# 04-mcu2.net
KiCad netlist of a schematic drawn in Altium Designer
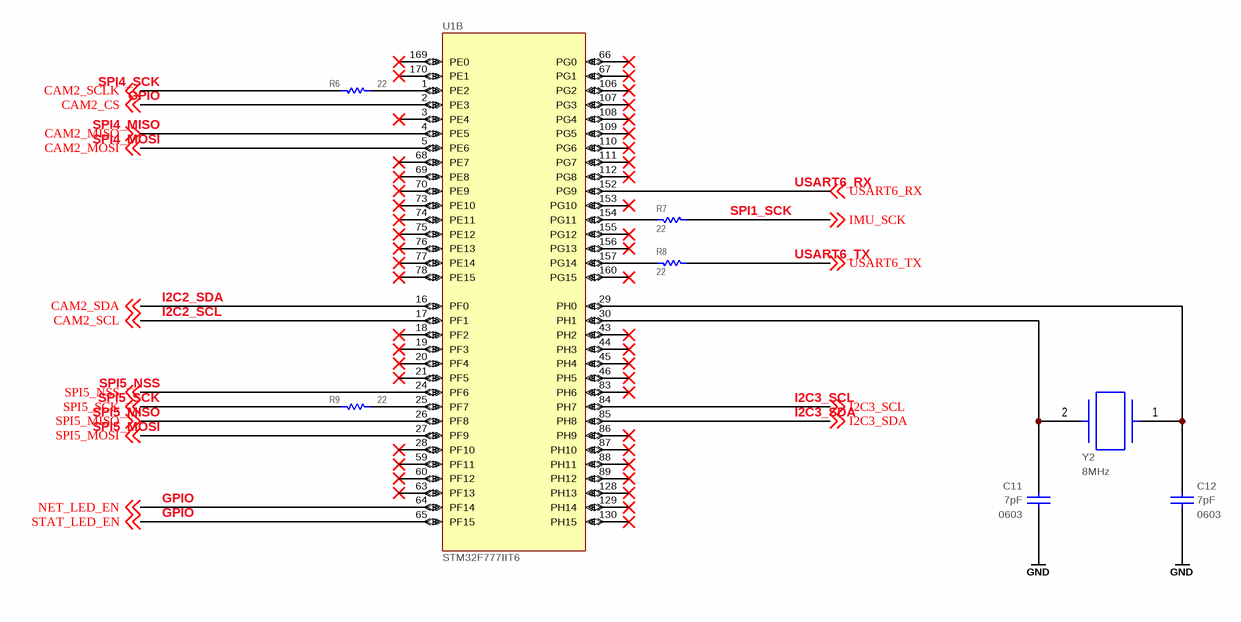
[diagram p0: 04-mcu2.SchDoc]

(export (version "E")
  (design (tool "Eeschema 10.0.6"))
  (components
    (comp (ref "C11")
      (value "7pF")
      (footprint "generic:CAPC160X80X90L20N")
      (description "Ceramic Capacitor 7pF +/-0.25pF 0603")
      (fields
        (field (name "MANUFACTURER") "Samsung")
        (field (name "TOLERANCE") "+/-0.25pF")
        (field (name "PACKAGE") "0603")
      )
      (libsource (lib "vishay") (part "CAP"))
    )
    (comp (ref "C12")
      (value "7pF")
      (footprint "generic:CAPC160X80X90L20N")
      (description "Ceramic Capacitor 7pF +/-0.25pF 0603")
      (fields
        (field (name "MANUFACTURER") "Samsung")
        (field (name "TOLERANCE") "+/-0.25pF")
        (field (name "PACKAGE") "0603")
      )
      (libsource (lib "vishay") (part "CAP"))
    )
    (comp (ref "R6")
      (value "22")
      (footprint "RESC2012X70N")
      (description "Thick Film Resistor 22 ±1% 0805")
      (fields (field (name "MANUFACTURER") "Panasonic") (field (name "TOLERANCE") "±1%"))
      (libsource (lib "Graviton") (part "RES 0402"))
    )
    (comp (ref "R7")
      (value "22")
      (footprint "RESC2012X70N")
      (description "Thick Film Resistor 22 ±1% 0805")
      (fields (field (name "MANUFACTURER") "Panasonic") (field (name "TOLERANCE") "±1%"))
      (libsource (lib "Graviton") (part "RES 0402"))
    )
    (comp (ref "R8")
      (value "22")
      (footprint "RESC2012X70N")
      (description "Thick Film Resistor 22 ±1% 0805")
      (fields (field (name "MANUFACTURER") "Panasonic") (field (name "TOLERANCE") "±1%"))
      (libsource (lib "Graviton") (part "RES 0402"))
    )
    (comp (ref "R9")
      (value "22")
      (footprint "RESC2012X70N")
      (description "Thick Film Resistor 22 ±1% 0805")
      (fields (field (name "MANUFACTURER") "Panasonic") (field (name "TOLERANCE") "±1%"))
      (libsource (lib "Graviton") (part "RES 0402"))
    )
    (comp (ref "U1")
      (value "STM32F777IIT6")
      (footprint "st:TSQFP50P2600X2600X160-176N")
      (description "Microcontroller")
      (fields (field (name "MANUFACTURER") "STMicroelectronics"))
      (libsource (lib "st") (part "STM32F777IIT"))
    )
    (comp (ref "Y2")
      (value "ABLS-8.000MHZ-B2-T")
      (footprint "ABLS")
      (description "CRYSTAL 8MHZ 18PF SMD")
      (fields (field (name "MANUFACTURER") "Abracon LLC") (field (name "FREQUENCY") "8MHz"))
      (libsource (lib "abracon") (part "ABLS-8.000MHZ-B2-T"))
    )
  )
  (nets
    (net (code "1") (name "CAM2_CS") (class "Default")
      (node (ref "U1") (pin "2") (pinfunction "PE3_2") (pintype "bidirectional"))
    )
    (net (code "2") (name "CAM2_MISO") (class "Default")
      (node (ref "U1") (pin "4") (pinfunction "PE5_4") (pintype "bidirectional"))
    )
    (net (code "3") (name "CAM2_MOSI") (class "Default")
      (node (ref "U1") (pin "5") (pinfunction "PE6_5") (pintype "bidirectional"))
    )
    (net (code "4") (name "CAM2_SCL") (class "Default")
      (node (ref "U1") (pin "17") (pinfunction "PF1_17") (pintype "bidirectional"))
    )
    (net (code "5") (name "CAM2_SCLK") (class "Default")
      (node (ref "R6") (pin "1") (pinfunction "1_1") (pintype "passive"))
    )
    (net (code "6") (name "CAM2_SDA") (class "Default")
      (node (ref "U1") (pin "16") (pinfunction "PF0_16") (pintype "bidirectional"))
    )
    (net (code "7") (name "GND") (class "Default")
      (node (ref "C11") (pin "1") (pinfunction "1_1") (pintype "passive"))
      (node (ref "C12") (pin "1") (pinfunction "1_1") (pintype "passive"))
    )
    (net (code "8") (name "I2C3_SCL") (class "Default")
      (node (ref "U1") (pin "84") (pinfunction "PH7_84") (pintype "bidirectional"))
    )
    (net (code "9") (name "I2C3_SDA") (class "Default")
      (node (ref "U1") (pin "85") (pinfunction "PH8_85") (pintype "bidirectional"))
    )
    (net (code "10") (name "IMU_SCK") (class "Default")
      (node (ref "R7") (pin "2") (pinfunction "2_2") (pintype "passive"))
    )
    (net (code "11") (name "NET_LED_EN") (class "Default")
      (node (ref "U1") (pin "64") (pinfunction "PF14_64") (pintype "bidirectional"))
    )
    (net (code "12") (name "Net-(U1B-PE2)") (class "Default")
      (node (ref "R6") (pin "2") (pinfunction "2_2") (pintype "passive"))
      (node (ref "U1") (pin "1") (pinfunction "PE2_1") (pintype "bidirectional"))
    )
    (net (code "13") (name "Net-(U1B-PF7)") (class "Default")
      (node (ref "R9") (pin "2") (pinfunction "2_2") (pintype "passive"))
      (node (ref "U1") (pin "25") (pinfunction "PF7_25") (pintype "bidirectional"))
    )
    (net (code "14") (name "Net-(U1B-PG11)") (class "Default")
      (node (ref "R7") (pin "1") (pinfunction "1_1") (pintype "passive"))
      (node (ref "U1") (pin "154") (pinfunction "PG11_154") (pintype "bidirectional"))
    )
    (net (code "15") (name "Net-(U1B-PG14)") (class "Default")
      (node (ref "R8") (pin "1") (pinfunction "1_1") (pintype "passive"))
      (node (ref "U1") (pin "157") (pinfunction "PG14_157") (pintype "bidirectional"))
    )
    (net (code "16") (name "Net-(U1B-PH0)") (class "Default")
      (node (ref "C12") (pin "2") (pinfunction "2_2") (pintype "passive"))
      (node (ref "U1") (pin "29") (pinfunction "PH0_29") (pintype "bidirectional"))
      (node (ref "Y2") (pin "1") (pinfunction "XTAL1_1") (pintype "passive"))
    )
    (net (code "17") (name "Net-(U1B-PH1)") (class "Default")
      (node (ref "C11") (pin "2") (pinfunction "2_2") (pintype "passive"))
      (node (ref "U1") (pin "30") (pinfunction "PH1_30") (pintype "bidirectional"))
      (node (ref "Y2") (pin "2") (pinfunction "XTAL2_2") (pintype "passive"))
    )
    (net (code "18") (name "SPI5_MISO") (class "Default")
      (node (ref "U1") (pin "26") (pinfunction "PF8_26") (pintype "bidirectional"))
    )
    (net (code "19") (name "SPI5_MOSI") (class "Default")
      (node (ref "U1") (pin "27") (pinfunction "PF9_27") (pintype "bidirectional"))
    )
    (net (code "20") (name "SPI5_NSS") (class "Default")
      (node (ref "U1") (pin "24") (pinfunction "PF6_24") (pintype "bidirectional"))
    )
    (net (code "21") (name "SPI5_SCK") (class "Default")
      (node (ref "R9") (pin "1") (pinfunction "1_1") (pintype "passive"))
    )
    (net (code "22") (name "STAT_LED_EN") (class "Default")
      (node (ref "U1") (pin "65") (pinfunction "PF15_65") (pintype "bidirectional"))
    )
    (net (code "23") (name "USART6_RX") (class "Default")
      (node (ref "U1") (pin "152") (pinfunction "PG9_152") (pintype "bidirectional"))
    )
    (net (code "24") (name "USART6_TX") (class "Default")
      (node (ref "R8") (pin "2") (pinfunction "2_2") (pintype "passive"))
    )
    (net (code "25") (name "unconnected-(U1B-PE0-Pad169)") (class "Default")
      (node (ref "U1") (pin "169") (pinfunction "PE0_169") (pintype "bidirectional+no_connect"))
    )
    (net (code "26") (name "unconnected-(U1B-PE1-Pad170)") (class "Default")
      (node (ref "U1") (pin "170") (pinfunction "PE1_170") (pintype "bidirectional+no_connect"))
    )
    (net (code "27") (name "unconnected-(U1B-PE4-Pad3)") (class "Default")
      (node (ref "U1") (pin "3") (pinfunction "PE4_3") (pintype "bidirectional+no_connect"))
    )
    (net (code "28") (name "unconnected-(U1B-PE7-Pad68)") (class "Default")
      (node (ref "U1") (pin "68") (pinfunction "PE7_68") (pintype "bidirectional+no_connect"))
    )
    (net (code "29") (name "unconnected-(U1B-PE8-Pad69)") (class "Default")
      (node (ref "U1") (pin "69") (pinfunction "PE8_69") (pintype "bidirectional+no_connect"))
    )
    (net (code "30") (name "unconnected-(U1B-PE9-Pad70)") (class "Default")
      (node (ref "U1") (pin "70") (pinfunction "PE9_70") (pintype "bidirectional+no_connect"))
    )
    (net (code "31") (name "unconnected-(U1B-PE10-Pad73)") (class "Default")
      (node (ref "U1") (pin "73") (pinfunction "PE10_73") (pintype "bidirectional+no_connect"))
    )
    (net (code "32") (name "unconnected-(U1B-PE11-Pad74)") (class "Default")
      (node (ref "U1") (pin "74") (pinfunction "PE11_74") (pintype "bidirectional+no_connect"))
    )
    (net (code "33") (name "unconnected-(U1B-PE12-Pad75)") (class "Default")
      (node (ref "U1") (pin "75") (pinfunction "PE12_75") (pintype "bidirectional+no_connect"))
    )
    (net (code "34") (name "unconnected-(U1B-PE13-Pad76)") (class "Default")
      (node (ref "U1") (pin "76") (pinfunction "PE13_76") (pintype "bidirectional+no_connect"))
    )
    (net (code "35") (name "unconnected-(U1B-PE14-Pad77)") (class "Default")
      (node (ref "U1") (pin "77") (pinfunction "PE14_77") (pintype "bidirectional+no_connect"))
    )
    (net (code "36") (name "unconnected-(U1B-PE15-Pad78)") (class "Default")
      (node (ref "U1") (pin "78") (pinfunction "PE15_78") (pintype "bidirectional+no_connect"))
    )
    (net (code "37") (name "unconnected-(U1B-PF2-Pad18)") (class "Default")
      (node (ref "U1") (pin "18") (pinfunction "PF2_18") (pintype "bidirectional+no_connect"))
    )
    (net (code "38") (name "unconnected-(U1B-PF3-Pad19)") (class "Default")
      (node (ref "U1") (pin "19") (pinfunction "PF3_19") (pintype "bidirectional+no_connect"))
    )
    (net (code "39") (name "unconnected-(U1B-PF4-Pad20)") (class "Default")
      (node (ref "U1") (pin "20") (pinfunction "PF4_20") (pintype "bidirectional+no_connect"))
    )
    (net (code "40") (name "unconnected-(U1B-PF5-Pad21)") (class "Default")
      (node (ref "U1") (pin "21") (pinfunction "PF5_21") (pintype "bidirectional+no_connect"))
    )
    (net (code "41") (name "unconnected-(U1B-PF10-Pad28)") (class "Default")
      (node (ref "U1") (pin "28") (pinfunction "PF10_28") (pintype "bidirectional+no_connect"))
    )
    (net (code "42") (name "unconnected-(U1B-PF11-Pad59)") (class "Default")
      (node (ref "U1") (pin "59") (pinfunction "PF11_59") (pintype "bidirectional+no_connect"))
    )
    (net (code "43") (name "unconnected-(U1B-PF12-Pad60)") (class "Default")
      (node (ref "U1") (pin "60") (pinfunction "PF12_60") (pintype "bidirectional+no_connect"))
    )
    (net (code "44") (name "unconnected-(U1B-PF13-Pad63)") (class "Default")
      (node (ref "U1") (pin "63") (pinfunction "PF13_63") (pintype "bidirectional+no_connect"))
    )
    (net (code "45") (name "unconnected-(U1B-PG0-Pad66)") (class "Default")
      (node (ref "U1") (pin "66") (pinfunction "PG0_66") (pintype "bidirectional+no_connect"))
    )
    (net (code "46") (name "unconnected-(U1B-PG1-Pad67)") (class "Default")
      (node (ref "U1") (pin "67") (pinfunction "PG1_67") (pintype "bidirectional+no_connect"))
    )
    (net (code "47") (name "unconnected-(U1B-PG2-Pad106)") (class "Default")
      (node (ref "U1") (pin "106") (pinfunction "PG2_106") (pintype "bidirectional+no_connect"))
    )
    (net (code "48") (name "unconnected-(U1B-PG3-Pad107)") (class "Default")
      (node (ref "U1") (pin "107") (pinfunction "PG3_107") (pintype "bidirectional+no_connect"))
    )
    (net (code "49") (name "unconnected-(U1B-PG4-Pad108)") (class "Default")
      (node (ref "U1") (pin "108") (pinfunction "PG4_108") (pintype "bidirectional+no_connect"))
    )
    (net (code "50") (name "unconnected-(U1B-PG5-Pad109)") (class "Default")
      (node (ref "U1") (pin "109") (pinfunction "PG5_109") (pintype "bidirectional+no_connect"))
    )
    (net (code "51") (name "unconnected-(U1B-PG6-Pad110)") (class "Default")
      (node (ref "U1") (pin "110") (pinfunction "PG6_110") (pintype "bidirectional+no_connect"))
    )
    (net (code "52") (name "unconnected-(U1B-PG7-Pad111)") (class "Default")
      (node (ref "U1") (pin "111") (pinfunction "PG7_111") (pintype "bidirectional+no_connect"))
    )
    (net (code "53") (name "unconnected-(U1B-PG8-Pad112)") (class "Default")
      (node (ref "U1") (pin "112") (pinfunction "PG8_112") (pintype "bidirectional+no_connect"))
    )
    (net (code "54") (name "unconnected-(U1B-PG10-Pad153)") (class "Default")
      (node (ref "U1") (pin "153") (pinfunction "PG10_153") (pintype "bidirectional+no_connect"))
    )
    (net (code "55") (name "unconnected-(U1B-PG12-Pad155)") (class "Default")
      (node (ref "U1") (pin "155") (pinfunction "PG12_155") (pintype "bidirectional+no_connect"))
    )
    (net (code "56") (name "unconnected-(U1B-PG13-Pad156)") (class "Default")
      (node (ref "U1") (pin "156") (pinfunction "PG13_156") (pintype "bidirectional+no_connect"))
    )
    (net (code "57") (name "unconnected-(U1B-PG15-Pad160)") (class "Default")
      (node (ref "U1") (pin "160") (pinfunction "PG15_160") (pintype "bidirectional+no_connect"))
    )
    (net (code "58") (name "unconnected-(U1B-PH2-Pad43)") (class "Default")
      (node (ref "U1") (pin "43") (pinfunction "PH2_43") (pintype "bidirectional+no_connect"))
    )
    (net (code "59") (name "unconnected-(U1B-PH3-Pad44)") (class "Default")
      (node (ref "U1") (pin "44") (pinfunction "PH3_44") (pintype "bidirectional+no_connect"))
    )
    (net (code "60") (name "unconnected-(U1B-PH4-Pad45)") (class "Default")
      (node (ref "U1") (pin "45") (pinfunction "PH4_45") (pintype "bidirectional+no_connect"))
    )
    (net (code "61") (name "unconnected-(U1B-PH5-Pad46)") (class "Default")
      (node (ref "U1") (pin "46") (pinfunction "PH5_46") (pintype "bidirectional+no_connect"))
    )
    (net (code "62") (name "unconnected-(U1B-PH6-Pad83)") (class "Default")
      (node (ref "U1") (pin "83") (pinfunction "PH6_83") (pintype "bidirectional+no_connect"))
    )
    (net (code "63") (name "unconnected-(U1B-PH9-Pad86)") (class "Default")
      (node (ref "U1") (pin "86") (pinfunction "PH9_86") (pintype "bidirectional+no_connect"))
    )
    (net (code "64") (name "unconnected-(U1B-PH10-Pad87)") (class "Default")
      (node (ref "U1") (pin "87") (pinfunction "PH10_87") (pintype "bidirectional+no_connect"))
    )
    (net (code "65") (name "unconnected-(U1B-PH11-Pad88)") (class "Default")
      (node (ref "U1") (pin "88") (pinfunction "PH11_88") (pintype "bidirectional+no_connect"))
    )
    (net (code "66") (name "unconnected-(U1B-PH12-Pad89)") (class "Default")
      (node (ref "U1") (pin "89") (pinfunction "PH12_89") (pintype "bidirectional+no_connect"))
    )
    (net (code "67") (name "unconnected-(U1B-PH13-Pad128)") (class "Default")
      (node (ref "U1") (pin "128") (pinfunction "PH13_128") (pintype "bidirectional+no_connect"))
    )
    (net (code "68") (name "unconnected-(U1B-PH14-Pad129)") (class "Default")
      (node (ref "U1") (pin "129") (pinfunction "PH14_129") (pintype "bidirectional+no_connect"))
    )
    (net (code "69") (name "unconnected-(U1B-PH15-Pad130)") (class "Default")
      (node (ref "U1") (pin "130") (pinfunction "PH15_130") (pintype "bidirectional+no_connect"))
    )
  )
)
